# Adafruit_USB_Type_C_Vertical_Breakout.net
KiCad netlist of a schematic drawn in EAGLE
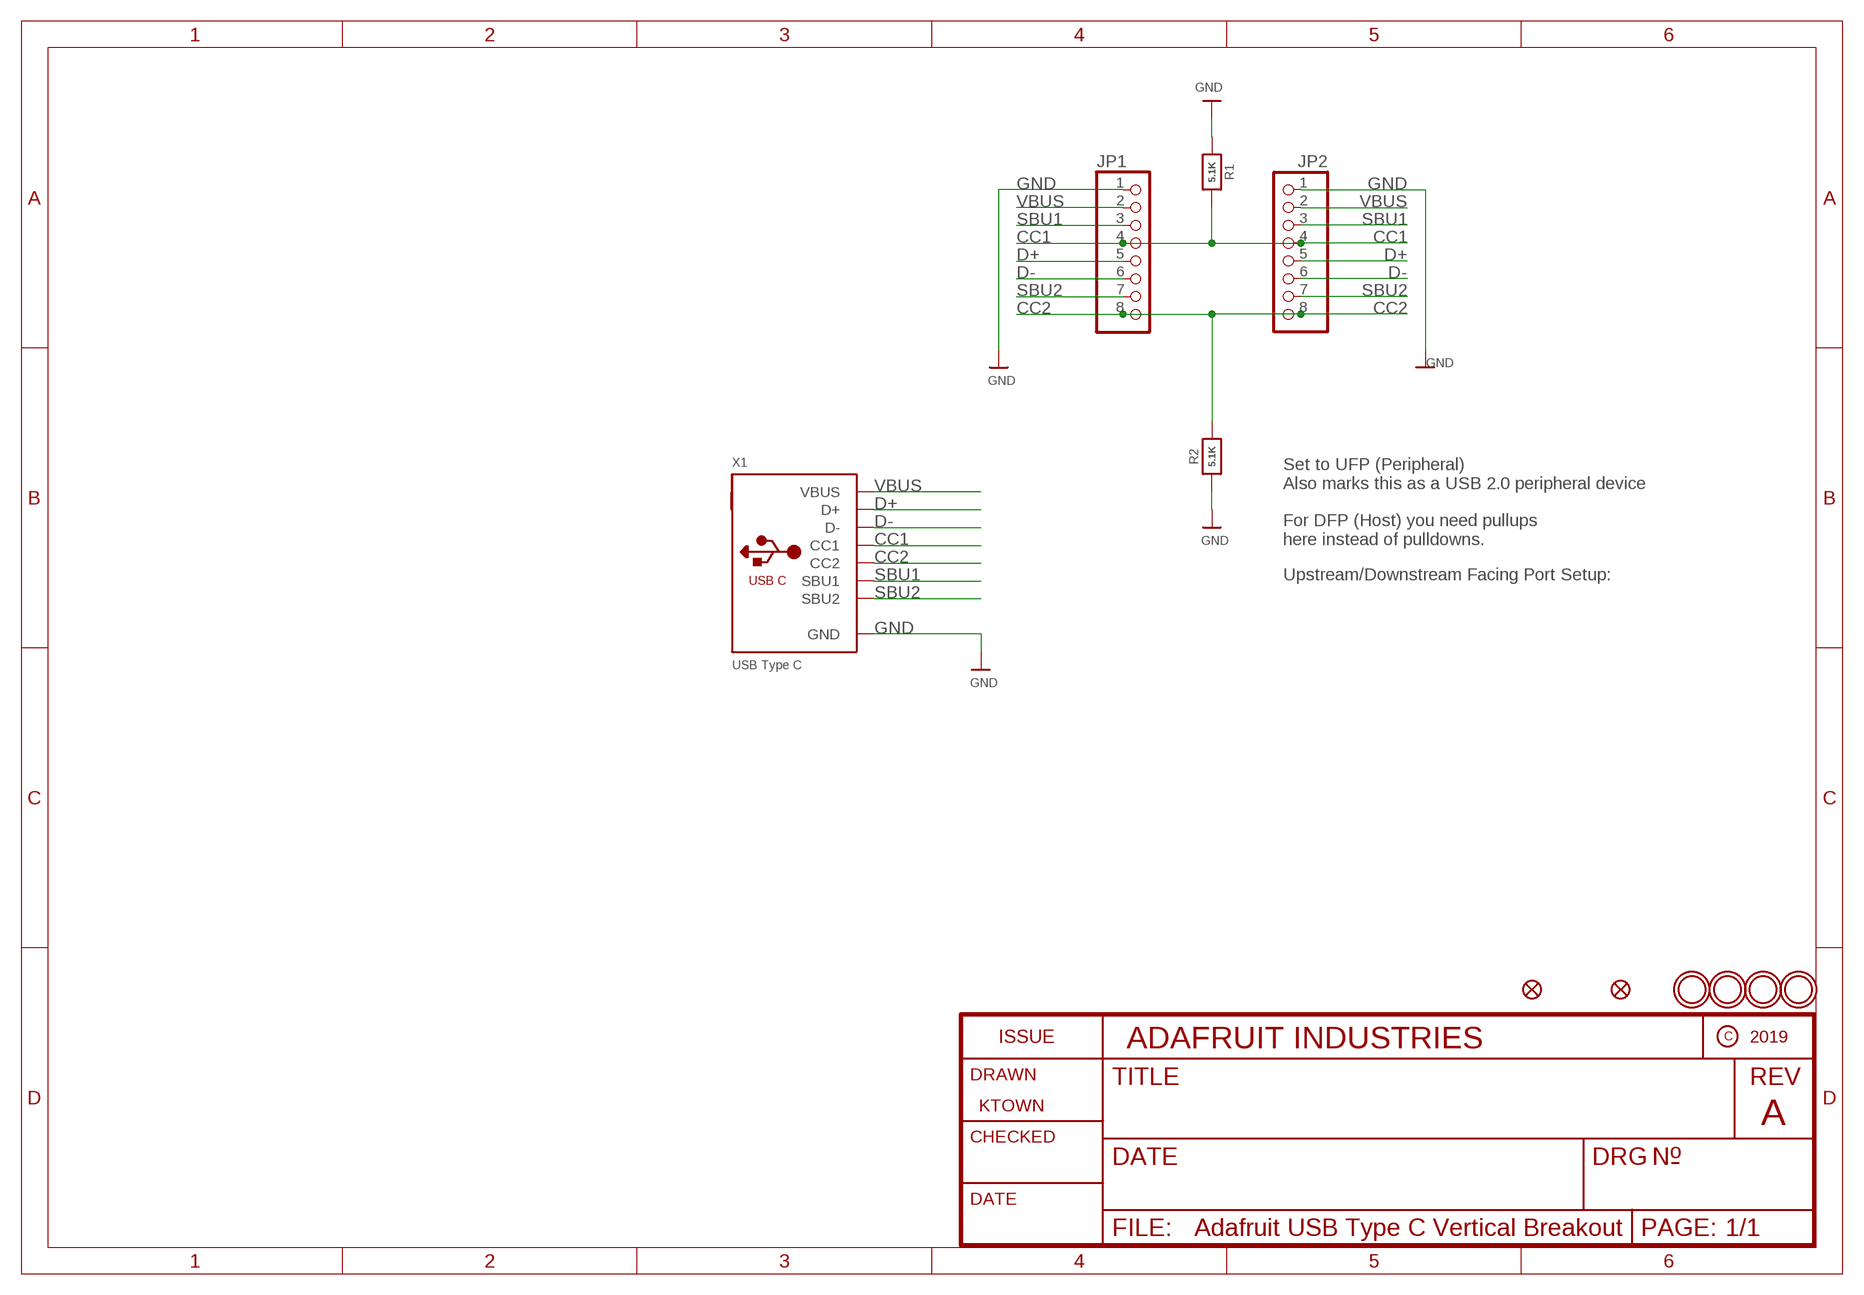
[diagram p0: schematic, sheet 1]

(export (version "E")
  (design (tool "Eeschema 10.0.6"))
  (components
    (comp (ref "FID1")
      (value "FIDUCIAL_1MM")
      (footprint "eagle-import:FIDUCIAL_1MM")
      (libsource (lib "eagle-import") (part "FIDUCIAL_1MM"))
    )
    (comp (ref "FID2")
      (value "FIDUCIAL_1MM")
      (footprint "eagle-import:FIDUCIAL_1MM")
      (libsource (lib "eagle-import") (part "FIDUCIAL_1MM"))
    )
    (comp (ref "JP1")
      (value "HEADER-1X876MIL")
      (footprint "eagle-import:1X08_ROUND_76")
      (libsource (lib "eagle-import") (part "HEADER-1X876MIL"))
    )
    (comp (ref "JP2")
      (value "HEADER-1X876MIL")
      (footprint "eagle-import:1X08_ROUND_76")
      (libsource (lib "eagle-import") (part "HEADER-1X876MIL"))
    )
    (comp (ref "R1")
      (value "5.1K")
      (footprint "eagle-import:0603-NO")
      (libsource (lib "eagle-import") (part "RESISTOR_0603_NOOUT"))
    )
    (comp (ref "R2")
      (value "5.1K")
      (footprint "eagle-import:0603-NO")
      (libsource (lib "eagle-import") (part "RESISTOR_0603_NOOUT"))
    )
    (comp (ref "U$1")
      (value "MOUNTINGHOLE2.5")
      (footprint "eagle-import:MOUNTINGHOLE_2.5_PLATED")
      (libsource (lib "eagle-import") (part "MOUNTINGHOLE2.5"))
    )
    (comp (ref "U$2")
      (value "MOUNTINGHOLE2.5")
      (footprint "eagle-import:MOUNTINGHOLE_2.5_PLATED")
      (libsource (lib "eagle-import") (part "MOUNTINGHOLE2.5"))
    )
    (comp (ref "U$10")
      (value "MOUNTINGHOLE2.5")
      (footprint "eagle-import:MOUNTINGHOLE_2.5_PLATED")
      (libsource (lib "eagle-import") (part "MOUNTINGHOLE2.5"))
    )
    (comp (ref "U$11")
      (value "MOUNTINGHOLE2.5")
      (footprint "eagle-import:MOUNTINGHOLE_2.5_PLATED")
      (libsource (lib "eagle-import") (part "MOUNTINGHOLE2.5"))
    )
    (comp (ref "X1")
      (value "USB Type C")
      (footprint "eagle-import:USB_C_VERTICAL")
      (libsource (lib "eagle-import") (part "USB_C_VERTICAL"))
    )
  )
  (nets
    (net (code "1") (name "/CC1") (class "Default")
      (node (ref "JP1") (pin "4") (pinfunction "4_4") (pintype "passive"))
      (node (ref "JP2") (pin "4") (pinfunction "4_4") (pintype "passive"))
      (node (ref "R1") (pin "2") (pinfunction "2_2") (pintype "passive"))
      (node (ref "X1") (pin "A5") (pinfunction "CC1_A5") (pintype "bidirectional"))
    )
    (net (code "2") (name "/CC2") (class "Default")
      (node (ref "JP1") (pin "8") (pinfunction "8_8") (pintype "passive"))
      (node (ref "JP2") (pin "8") (pinfunction "8_8") (pintype "passive"))
      (node (ref "R2") (pin "2") (pinfunction "2_2") (pintype "passive"))
      (node (ref "X1") (pin "B5") (pinfunction "CC2_B5") (pintype "bidirectional"))
    )
    (net (code "3") (name "/D+") (class "Default")
      (node (ref "JP1") (pin "5") (pinfunction "5_5") (pintype "passive"))
      (node (ref "JP2") (pin "5") (pinfunction "5_5") (pintype "passive"))
      (node (ref "X1") (pin "A6") (pinfunction "D+_A6") (pintype "bidirectional"))
      (node (ref "X1") (pin "B6") (pinfunction "D+_B6") (pintype "bidirectional"))
    )
    (net (code "4") (name "/D-") (class "Default")
      (node (ref "JP1") (pin "6") (pinfunction "6_6") (pintype "passive"))
      (node (ref "JP2") (pin "6") (pinfunction "6_6") (pintype "passive"))
      (node (ref "X1") (pin "A7") (pinfunction "D-_A7") (pintype "bidirectional"))
      (node (ref "X1") (pin "B7") (pinfunction "D-_B7") (pintype "bidirectional"))
    )
    (net (code "5") (name "/SBU1") (class "Default")
      (node (ref "JP1") (pin "3") (pinfunction "3_3") (pintype "passive"))
      (node (ref "JP2") (pin "3") (pinfunction "3_3") (pintype "passive"))
      (node (ref "X1") (pin "A8") (pinfunction "SBU1_A8") (pintype "bidirectional"))
    )
    (net (code "6") (name "/SBU2") (class "Default")
      (node (ref "JP1") (pin "7") (pinfunction "7_7") (pintype "passive"))
      (node (ref "JP2") (pin "7") (pinfunction "7_7") (pintype "passive"))
      (node (ref "X1") (pin "B8") (pinfunction "SBU2_B8") (pintype "bidirectional"))
    )
    (net (code "7") (name "/VBUS") (class "Default")
      (node (ref "JP1") (pin "2") (pinfunction "2_2") (pintype "passive"))
      (node (ref "JP2") (pin "2") (pinfunction "2_2") (pintype "passive"))
      (node (ref "X1") (pin "A4") (pinfunction "VBUS_A4") (pintype "power_in"))
      (node (ref "X1") (pin "A9") (pinfunction "VBUS_A9") (pintype "power_in"))
      (node (ref "X1") (pin "B4") (pinfunction "VBUS_B4") (pintype "power_in"))
      (node (ref "X1") (pin "B9") (pinfunction "VBUS_B9") (pintype "power_in"))
    )
    (net (code "8") (name "GND") (class "Default")
      (node (ref "JP1") (pin "1") (pinfunction "1_1") (pintype "passive"))
      (node (ref "JP2") (pin "1") (pinfunction "1_1") (pintype "passive"))
      (node (ref "R1") (pin "1") (pinfunction "1_1") (pintype "passive"))
      (node (ref "R2") (pin "1") (pinfunction "1_1") (pintype "passive"))
      (node (ref "X1") (pin "A1") (pinfunction "GND_A1") (pintype "power_in"))
      (node (ref "X1") (pin "A12") (pinfunction "GND_A12") (pintype "power_in"))
      (node (ref "X1") (pin "B1") (pinfunction "GND_B1") (pintype "power_in"))
      (node (ref "X1") (pin "B12") (pinfunction "GND_B12") (pintype "power_in"))
      (node (ref "X1") (pin "P$1") (pinfunction "GND_P$1") (pintype "power_in"))
      (node (ref "X1") (pin "P$2") (pinfunction "GND_P$2") (pintype "power_in"))
      (node (ref "X1") (pin "P$3") (pinfunction "GND_P$3") (pintype "power_in"))
      (node (ref "X1") (pin "P$4") (pinfunction "GND_P$4") (pintype "power_in"))
    )
  )
)
